# Base_Buck_Schematic.net
KiCad netlist of a schematic drawn in Altium Designer
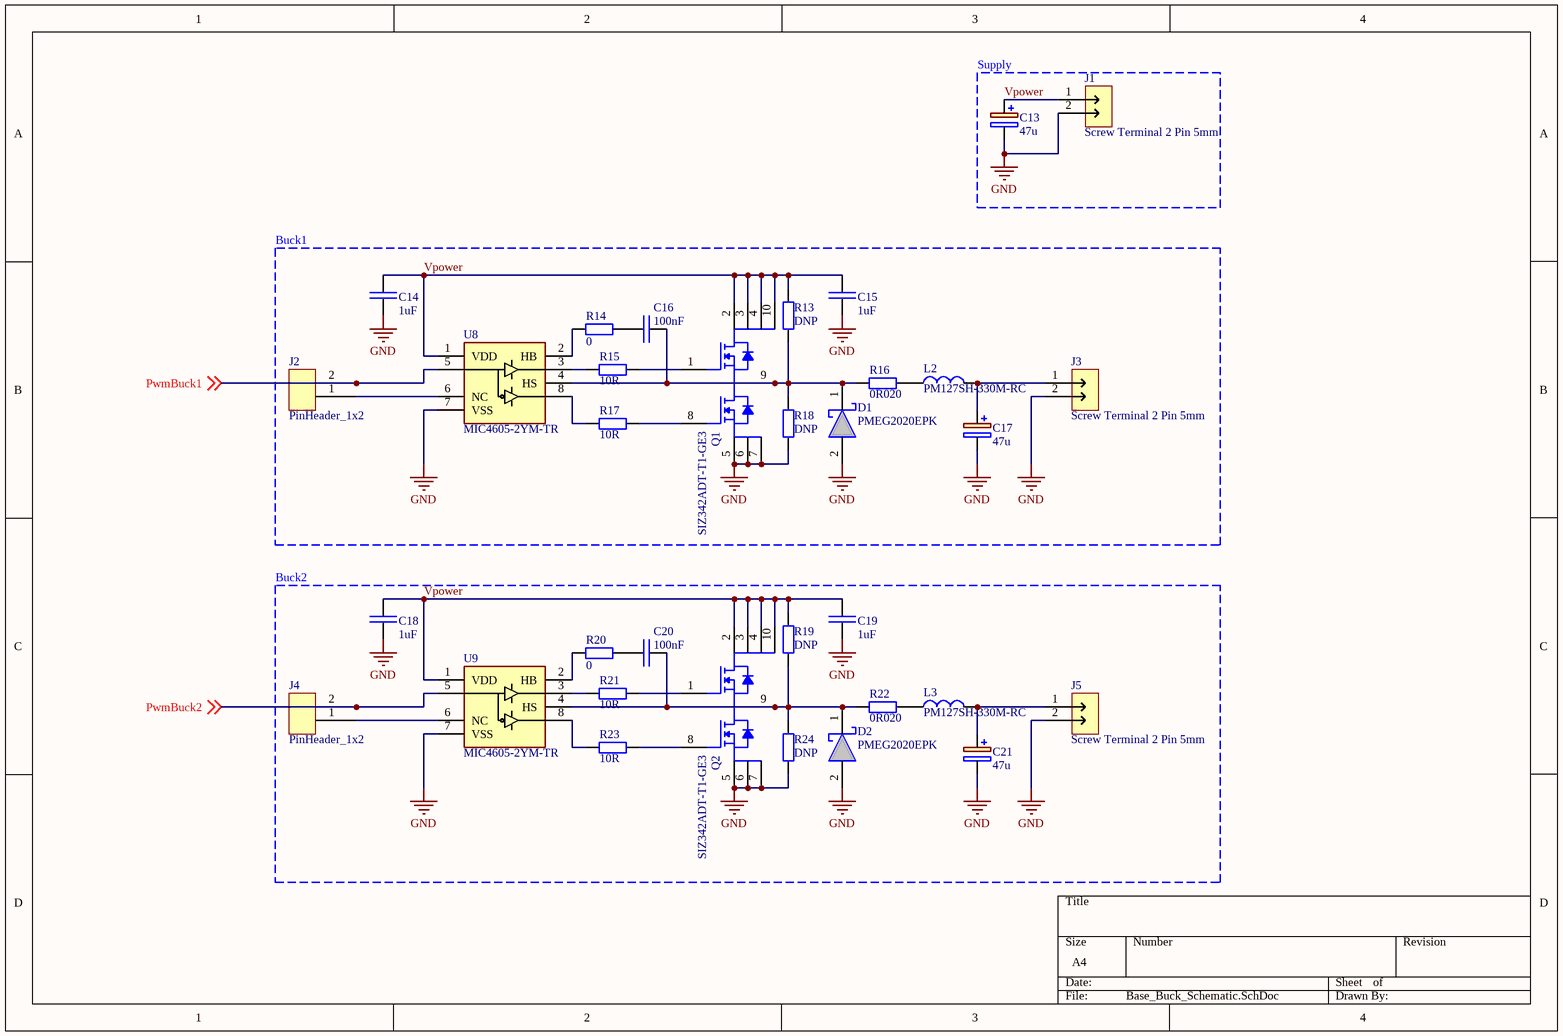
[diagram p0: Base_Buck_Schematic.SchDoc]

(export (version "E")
  (design (tool "Eeschema 10.0.6"))
  (components
    (comp (ref "C13")
      (value "47u")
      (footprint "CAPAE7366X61N")
      (description "Aluminium Electrolytic Capacitors - SMD 47uF 25V")
      (libsource (lib "Base_Symbols") (part "EEE-FK1E470P"))
    )
    (comp (ref "C14")
      (value "1uF")
      (footprint "CAP_SM0805_YAGEOCC2_N")
      (description "CAP 1uF SM0805 X7R 25V YAGEO CC2")
      (fields
        (field (name "MANUFACTURER") "Yageo")
        (field (name "MANUFACTURER PART NUMBER") "CC0805KKX7R8BB105")
      )
      (libsource (lib "Base_Symbols") (part "CC0805KKX7R8BB105"))
    )
    (comp (ref "C15")
      (value "1uF")
      (footprint "CAP_SM0805_YAGEOCC2_N")
      (description "CAP 1uF SM0805 X7R 25V YAGEO CC2")
      (fields
        (field (name "MANUFACTURER") "Yageo")
        (field (name "MANUFACTURER PART NUMBER") "CC0805KKX7R8BB105")
      )
      (libsource (lib "Base_Symbols") (part "CC0805KKX7R8BB105"))
    )
    (comp (ref "C16")
      (value "100nF")
      (footprint "CAP_SM0603_YAGEOCC2_N")
      (description "CAP 100nF SM0603 X7R 50V YAGEO CC2")
      (fields
        (field (name "MANUFACTURER") "Yageo")
        (field (name "MANUFACTURER PART NUMBER") "CC0603KRX7R9BB104")
      )
      (libsource (lib "Base_Symbols") (part "CC0603KRX7R9BB104"))
    )
    (comp (ref "C17")
      (value "47u")
      (footprint "CAPAE7366X61N")
      (description "Aluminium Electrolytic Capacitors - SMD 47uF 25V")
      (libsource (lib "Base_Symbols") (part "EEE-FK1E470P"))
    )
    (comp (ref "C18")
      (value "1uF")
      (footprint "CAP_SM0805_YAGEOCC2_N")
      (description "CAP 1uF SM0805 X7R 25V YAGEO CC2")
      (fields
        (field (name "MANUFACTURER") "Yageo")
        (field (name "MANUFACTURER PART NUMBER") "CC0805KKX7R8BB105")
      )
      (libsource (lib "Base_Symbols") (part "CC0805KKX7R8BB105"))
    )
    (comp (ref "C19")
      (value "1uF")
      (footprint "CAP_SM0805_YAGEOCC2_N")
      (description "CAP 1uF SM0805 X7R 25V YAGEO CC2")
      (fields
        (field (name "MANUFACTURER") "Yageo")
        (field (name "MANUFACTURER PART NUMBER") "CC0805KKX7R8BB105")
      )
      (libsource (lib "Base_Symbols") (part "CC0805KKX7R8BB105"))
    )
    (comp (ref "C20")
      (value "100nF")
      (footprint "CAP_SM0603_YAGEOCC2_N")
      (description "CAP 100nF SM0603 X7R 50V YAGEO CC2")
      (fields
        (field (name "MANUFACTURER") "Yageo")
        (field (name "MANUFACTURER PART NUMBER") "CC0603KRX7R9BB104")
      )
      (libsource (lib "Base_Symbols") (part "CC0603KRX7R9BB104"))
    )
    (comp (ref "C21")
      (value "47u")
      (footprint "CAPAE7366X61N")
      (description "Aluminium Electrolytic Capacitors - SMD 47uF 25V")
      (libsource (lib "Base_Symbols") (part "EEE-FK1E470P"))
    )
    (comp (ref "D1")
      (value "PMEG2020EPK")
      (footprint "PMEG2020EPK")
      (description "PMEG2020EPK 20 V, 2 A low VF MEGA Schottky barrier rectifier")
      (libsource (lib "Base_Symbols") (part "PMEG2020EPK"))
    )
    (comp (ref "D2")
      (value "PMEG2020EPK")
      (footprint "PMEG2020EPK")
      (description "PMEG2020EPK 20 V, 2 A low VF MEGA Schottky barrier rectifier")
      (libsource (lib "Base_Symbols") (part "PMEG2020EPK"))
    )
    (comp (ref "J1")
      (value "Screw Terminal 2 Pin 5mm")
      (footprint "TB00250002BE")
      (libsource (lib "Base_Symbols") (part "TB00250002BE"))
    )
    (comp (ref "J2")
      (value "PinHeader_1x2")
      (footprint "PinHeader_1x2_2.54mm")
      (description "PinHeader_1x2 2.54mm Pitch")
      (libsource (lib "Base_Symbols") (part "PinHeader_1x2_2.54mm"))
    )
    (comp (ref "J3")
      (value "Screw Terminal 2 Pin 5mm")
      (footprint "TB00250002BE")
      (libsource (lib "Base_Symbols") (part "TB00250002BE"))
    )
    (comp (ref "J4")
      (value "PinHeader_1x2")
      (footprint "PinHeader_1x2_2.54mm")
      (description "PinHeader_1x2 2.54mm Pitch")
      (libsource (lib "Base_Symbols") (part "PinHeader_1x2_2.54mm"))
    )
    (comp (ref "J5")
      (value "Screw Terminal 2 Pin 5mm")
      (footprint "TB00250002BE")
      (libsource (lib "Base_Symbols") (part "TB00250002BE"))
    )
    (comp (ref "L2")
      (value "PM127SH-330M-RC")
      (footprint "PM127SH330MRC")
      (fields (field (name "MOUSER PART NUMBER") "542-PM127SH-330M-RC"))
      (libsource (lib "Base_Symbols") (part "PM127SH-330M-RC"))
    )
    (comp (ref "L3")
      (value "PM127SH-330M-RC")
      (footprint "PM127SH330MRC")
      (fields (field (name "MOUSER PART NUMBER") "542-PM127SH-330M-RC"))
      (libsource (lib "Base_Symbols") (part "PM127SH-330M-RC"))
    )
    (comp (ref "Q1")
      (value "SIZ342ADT-T1-GE3")
      (footprint "SIZ342ADT-T1-GE3")
      (description "MOSFET 30V Vds 20V Vgs PowerPAIR 3 x 3")
      (fields (field (name "MOUSER PART NUMBER") "78-SIZ342ADT-T1-GE3"))
      (libsource (lib "Base_Symbols") (part "SIZ342ADT-T1-GE3"))
    )
    (comp (ref "Q2")
      (value "SIZ342ADT-T1-GE3")
      (footprint "SIZ342ADT-T1-GE3")
      (description "MOSFET 30V Vds 20V Vgs PowerPAIR 3 x 3")
      (fields (field (name "MOUSER PART NUMBER") "78-SIZ342ADT-T1-GE3"))
      (libsource (lib "Base_Symbols") (part "SIZ342ADT-T1-GE3"))
    )
    (comp (ref "R13")
      (value "DNP")
      (footprint "RES_SM0603_YAGEORC_N")
      (description "RES 3K3 SM0603 YAGEO RC_L")
      (fields
        (field (name "MANUFACTURER") "Yageo")
        (field (name "MANUFACTURER PART NUMBER") "RC0603FR-0710KL")
      )
      (libsource (lib "Base_Symbols") (part "RC0603FR-073K3L"))
    )
    (comp (ref "R14")
      (value "0")
      (footprint "RES_SM0603_YAGEORC_N")
      (description "RES 0R SM0603 YAGEO RC_L")
      (fields
        (field (name "MANUFACTURER") "Yageo")
        (field (name "MANUFACTURER PART NUMBER") "RC0603FR-0710KL")
      )
      (libsource (lib "Base_Symbols") (part "RC0603FR-070RL"))
    )
    (comp (ref "R15")
      (value "10R")
      (footprint "RES_SM0603_YAGEORC_N")
      (description "RES 10R SM0603 YAGEO RC_L")
      (fields
        (field (name "MANUFACTURER") "Yageo")
        (field (name "MANUFACTURER PART NUMBER") "RC0603FR-0710RL")
      )
      (libsource (lib "Base_Symbols") (part "RC0603FR-0710RL"))
    )
    (comp (ref "R16")
      (value "0R020")
      (footprint "MSMA2512R0200FGN")
      (description "RES SM0603YAGEO RC_L")
      (libsource (lib "Base_Symbols") (part "MSMA2512R0200FGN"))
    )
    (comp (ref "R17")
      (value "10R")
      (footprint "RES_SM0603_YAGEORC_N")
      (description "RES 10R SM0603 YAGEO RC_L")
      (fields
        (field (name "MANUFACTURER") "Yageo")
        (field (name "MANUFACTURER PART NUMBER") "RC0603FR-0710RL")
      )
      (libsource (lib "Base_Symbols") (part "RC0603FR-0710RL"))
    )
    (comp (ref "R18")
      (value "DNP")
      (footprint "RES_SM0603_YAGEORC_N")
      (description "RES 3K3 SM0603 YAGEO RC_L")
      (fields
        (field (name "MANUFACTURER") "Yageo")
        (field (name "MANUFACTURER PART NUMBER") "RC0603FR-0710KL")
      )
      (libsource (lib "Base_Symbols") (part "RC0603FR-073K3L"))
    )
    (comp (ref "R19")
      (value "DNP")
      (footprint "RES_SM0603_YAGEORC_N")
      (description "RES 3K3 SM0603 YAGEO RC_L")
      (fields
        (field (name "MANUFACTURER") "Yageo")
        (field (name "MANUFACTURER PART NUMBER") "RC0603FR-0710KL")
      )
      (libsource (lib "Base_Symbols") (part "RC0603FR-073K3L"))
    )
    (comp (ref "R20")
      (value "0")
      (footprint "RES_SM0603_YAGEORC_N")
      (description "RES 0R SM0603 YAGEO RC_L")
      (fields
        (field (name "MANUFACTURER") "Yageo")
        (field (name "MANUFACTURER PART NUMBER") "RC0603FR-0710KL")
      )
      (libsource (lib "Base_Symbols") (part "RC0603FR-070RL"))
    )
    (comp (ref "R21")
      (value "10R")
      (footprint "RES_SM0603_YAGEORC_N")
      (description "RES 10R SM0603 YAGEO RC_L")
      (fields
        (field (name "MANUFACTURER") "Yageo")
        (field (name "MANUFACTURER PART NUMBER") "RC0603FR-0710RL")
      )
      (libsource (lib "Base_Symbols") (part "RC0603FR-0710RL"))
    )
    (comp (ref "R22")
      (value "0R020")
      (footprint "MSMA2512R0200FGN")
      (description "RES SM0603YAGEO RC_L")
      (libsource (lib "Base_Symbols") (part "MSMA2512R0200FGN"))
    )
    (comp (ref "R23")
      (value "10R")
      (footprint "RES_SM0603_YAGEORC_N")
      (description "RES 10R SM0603 YAGEO RC_L")
      (fields
        (field (name "MANUFACTURER") "Yageo")
        (field (name "MANUFACTURER PART NUMBER") "RC0603FR-0710RL")
      )
      (libsource (lib "Base_Symbols") (part "RC0603FR-0710RL"))
    )
    (comp (ref "R24")
      (value "DNP")
      (footprint "RES_SM0603_YAGEORC_N")
      (description "RES 3K3 SM0603 YAGEO RC_L")
      (fields
        (field (name "MANUFACTURER") "Yageo")
        (field (name "MANUFACTURER PART NUMBER") "RC0603FR-0710KL")
      )
      (libsource (lib "Base_Symbols") (part "RC0603FR-073K3L"))
    )
    (comp (ref "U8")
      (value "MIC4605-2YM-TR")
      (footprint "SOIC127P600X163-8N")
      (description "Gate Drivers 85V Half Bridge MOSFET Driver")
      (fields (field (name "MOUSER PART NUMBER") "998-MIC4605-2YM-TR"))
      (libsource (lib "Base_Symbols") (part "MIC4605-2YM-TR"))
    )
    (comp (ref "U9")
      (value "MIC4605-2YM-TR")
      (footprint "SOIC127P600X163-8N")
      (description "Gate Drivers 85V Half Bridge MOSFET Driver")
      (fields (field (name "MOUSER PART NUMBER") "998-MIC4605-2YM-TR"))
      (libsource (lib "Base_Symbols") (part "MIC4605-2YM-TR"))
    )
  )
  (nets
    (net (code "1") (name "/Vpower") (class "Default")
      (node (ref "C13") (pin "1") (pinfunction "+_1") (pintype "passive"))
      (node (ref "C14") (pin "1") (pintype "passive"))
      (node (ref "C15") (pin "1") (pintype "passive"))
      (node (ref "C18") (pin "1") (pintype "passive"))
      (node (ref "C19") (pin "1") (pintype "passive"))
      (node (ref "J1") (pin "1") (pinfunction "1_1") (pintype "passive"))
      (node (ref "Q1") (pin "10") (pinfunction "D_10") (pintype "passive"))
      (node (ref "Q1") (pin "2") (pinfunction "D_2") (pintype "passive"))
      (node (ref "Q1") (pin "3") (pinfunction "D_3") (pintype "passive"))
      (node (ref "Q1") (pin "4") (pinfunction "D_4") (pintype "passive"))
      (node (ref "Q2") (pin "10") (pinfunction "D_10") (pintype "passive"))
      (node (ref "Q2") (pin "2") (pinfunction "D_2") (pintype "passive"))
      (node (ref "Q2") (pin "3") (pinfunction "D_3") (pintype "passive"))
      (node (ref "Q2") (pin "4") (pinfunction "D_4") (pintype "passive"))
      (node (ref "R13") (pin "2") (pintype "passive"))
      (node (ref "R19") (pin "2") (pintype "passive"))
      (node (ref "U8") (pin "1") (pinfunction "VDD_1") (pintype "passive"))
      (node (ref "U9") (pin "1") (pinfunction "VDD_1") (pintype "passive"))
    )
    (net (code "2") (name "GND") (class "Default")
      (node (ref "C13") (pin "2") (pinfunction "-_2") (pintype "passive"))
      (node (ref "C14") (pin "2") (pintype "passive"))
      (node (ref "C15") (pin "2") (pintype "passive"))
      (node (ref "C17") (pin "2") (pinfunction "-_2") (pintype "passive"))
      (node (ref "C18") (pin "2") (pintype "passive"))
      (node (ref "C19") (pin "2") (pintype "passive"))
      (node (ref "C21") (pin "2") (pinfunction "-_2") (pintype "passive"))
      (node (ref "D1") (pin "2") (pinfunction "Anode_2") (pintype "passive"))
      (node (ref "D2") (pin "2") (pinfunction "Anode_2") (pintype "passive"))
      (node (ref "J1") (pin "2") (pinfunction "2_2") (pintype "passive"))
      (node (ref "J3") (pin "2") (pinfunction "2_2") (pintype "passive"))
      (node (ref "J5") (pin "2") (pinfunction "2_2") (pintype "passive"))
      (node (ref "Q1") (pin "5") (pinfunction "D_5") (pintype "passive"))
      (node (ref "Q1") (pin "6") (pinfunction "D_6") (pintype "passive"))
      (node (ref "Q1") (pin "7") (pinfunction "D_7") (pintype "passive"))
      (node (ref "Q2") (pin "5") (pinfunction "D_5") (pintype "passive"))
      (node (ref "Q2") (pin "6") (pinfunction "D_6") (pintype "passive"))
      (node (ref "Q2") (pin "7") (pinfunction "D_7") (pintype "passive"))
      (node (ref "R18") (pin "1") (pintype "passive"))
      (node (ref "R24") (pin "1") (pintype "passive"))
      (node (ref "U8") (pin "7") (pinfunction "VSS_7") (pintype "passive"))
      (node (ref "U9") (pin "7") (pinfunction "VSS_7") (pintype "passive"))
    )
    (net (code "3") (name "Net-(C16-Pad1)") (class "Default")
      (node (ref "C16") (pin "1") (pintype "passive"))
      (node (ref "R14") (pin "2") (pintype "passive"))
    )
    (net (code "4") (name "Net-(C17-+)") (class "Default")
      (node (ref "C17") (pin "1") (pinfunction "+_1") (pintype "passive"))
      (node (ref "J3") (pin "1") (pinfunction "1_1") (pintype "passive"))
      (node (ref "L2") (pin "2") (pinfunction "2_2") (pintype "passive"))
    )
    (net (code "5") (name "Net-(C20-Pad1)") (class "Default")
      (node (ref "C20") (pin "1") (pintype "passive"))
      (node (ref "R20") (pin "2") (pintype "passive"))
    )
    (net (code "6") (name "Net-(C21-+)") (class "Default")
      (node (ref "C21") (pin "1") (pinfunction "+_1") (pintype "passive"))
      (node (ref "J5") (pin "1") (pinfunction "1_1") (pintype "passive"))
      (node (ref "L3") (pin "2") (pinfunction "2_2") (pintype "passive"))
    )
    (net (code "7") (name "Net-(D1-Cathode)") (class "Default")
      (node (ref "C16") (pin "2") (pintype "passive"))
      (node (ref "D1") (pin "1") (pinfunction "Cathode_1") (pintype "passive"))
      (node (ref "Q1") (pin "9") (pinfunction "D_9") (pintype "passive"))
      (node (ref "R13") (pin "1") (pintype "passive"))
      (node (ref "R16") (pin "2") (pintype "passive"))
      (node (ref "R18") (pin "2") (pintype "passive"))
      (node (ref "U8") (pin "4") (pinfunction "HS_4") (pintype "passive"))
    )
    (net (code "8") (name "Net-(D2-Cathode)") (class "Default")
      (node (ref "C20") (pin "2") (pintype "passive"))
      (node (ref "D2") (pin "1") (pinfunction "Cathode_1") (pintype "passive"))
      (node (ref "Q2") (pin "9") (pinfunction "D_9") (pintype "passive"))
      (node (ref "R19") (pin "1") (pintype "passive"))
      (node (ref "R22") (pin "2") (pintype "passive"))
      (node (ref "R24") (pin "2") (pintype "passive"))
      (node (ref "U9") (pin "4") (pinfunction "HS_4") (pintype "passive"))
    )
    (net (code "9") (name "Net-(L2-Pad1)") (class "Default")
      (node (ref "L2") (pin "1") (pinfunction "1_1") (pintype "passive"))
      (node (ref "R16") (pin "1") (pintype "passive"))
    )
    (net (code "10") (name "Net-(L3-Pad1)") (class "Default")
      (node (ref "L3") (pin "1") (pinfunction "1_1") (pintype "passive"))
      (node (ref "R22") (pin "1") (pintype "passive"))
    )
    (net (code "11") (name "Net-(Q1-G1)") (class "Default")
      (node (ref "Q1") (pin "1") (pinfunction "G1_1") (pintype "passive"))
      (node (ref "R15") (pin "2") (pintype "passive"))
    )
    (net (code "12") (name "Net-(Q1-G2)") (class "Default")
      (node (ref "Q1") (pin "8") (pinfunction "G2_8") (pintype "passive"))
      (node (ref "R17") (pin "2") (pintype "passive"))
    )
    (net (code "13") (name "Net-(Q2-G1)") (class "Default")
      (node (ref "Q2") (pin "1") (pinfunction "G1_1") (pintype "passive"))
      (node (ref "R21") (pin "2") (pintype "passive"))
    )
    (net (code "14") (name "Net-(Q2-G2)") (class "Default")
      (node (ref "Q2") (pin "8") (pinfunction "G2_8") (pintype "passive"))
      (node (ref "R23") (pin "2") (pintype "passive"))
    )
    (net (code "15") (name "Net-(U8-HB)") (class "Default")
      (node (ref "R14") (pin "1") (pintype "passive"))
      (node (ref "U8") (pin "2") (pinfunction "HB_2") (pintype "passive"))
    )
    (net (code "16") (name "Net-(U8-HO)") (class "Default")
      (node (ref "R15") (pin "1") (pintype "passive"))
      (node (ref "U8") (pin "3") (pinfunction "HO_3") (pintype "passive"))
    )
    (net (code "17") (name "Net-(U8-LO)") (class "Default")
      (node (ref "R17") (pin "1") (pintype "passive"))
      (node (ref "U8") (pin "8") (pinfunction "LO_8") (pintype "passive"))
    )
    (net (code "18") (name "Net-(U8-NC)") (class "Default")
      (node (ref "J2") (pin "1") (pintype "passive"))
      (node (ref "U8") (pin "6") (pinfunction "NC_6") (pintype "passive"))
    )
    (net (code "19") (name "Net-(U9-HB)") (class "Default")
      (node (ref "R20") (pin "1") (pintype "passive"))
      (node (ref "U9") (pin "2") (pinfunction "HB_2") (pintype "passive"))
    )
    (net (code "20") (name "Net-(U9-HO)") (class "Default")
      (node (ref "R21") (pin "1") (pintype "passive"))
      (node (ref "U9") (pin "3") (pinfunction "HO_3") (pintype "passive"))
    )
    (net (code "21") (name "Net-(U9-LO)") (class "Default")
      (node (ref "R23") (pin "1") (pintype "passive"))
      (node (ref "U9") (pin "8") (pinfunction "LO_8") (pintype "passive"))
    )
    (net (code "22") (name "Net-(U9-NC)") (class "Default")
      (node (ref "J4") (pin "1") (pintype "passive"))
      (node (ref "U9") (pin "6") (pinfunction "NC_6") (pintype "passive"))
    )
    (net (code "23") (name "PwmBuck1") (class "Default")
      (node (ref "J2") (pin "2") (pintype "passive"))
      (node (ref "U8") (pin "5") (pinfunction "PWM_5") (pintype "passive"))
    )
    (net (code "24") (name "PwmBuck2") (class "Default")
      (node (ref "J4") (pin "2") (pintype "passive"))
      (node (ref "U9") (pin "5") (pinfunction "PWM_5") (pintype "passive"))
    )
  )
)
